# MEMS.net
KiCad netlist of a schematic drawn in Altium Designer
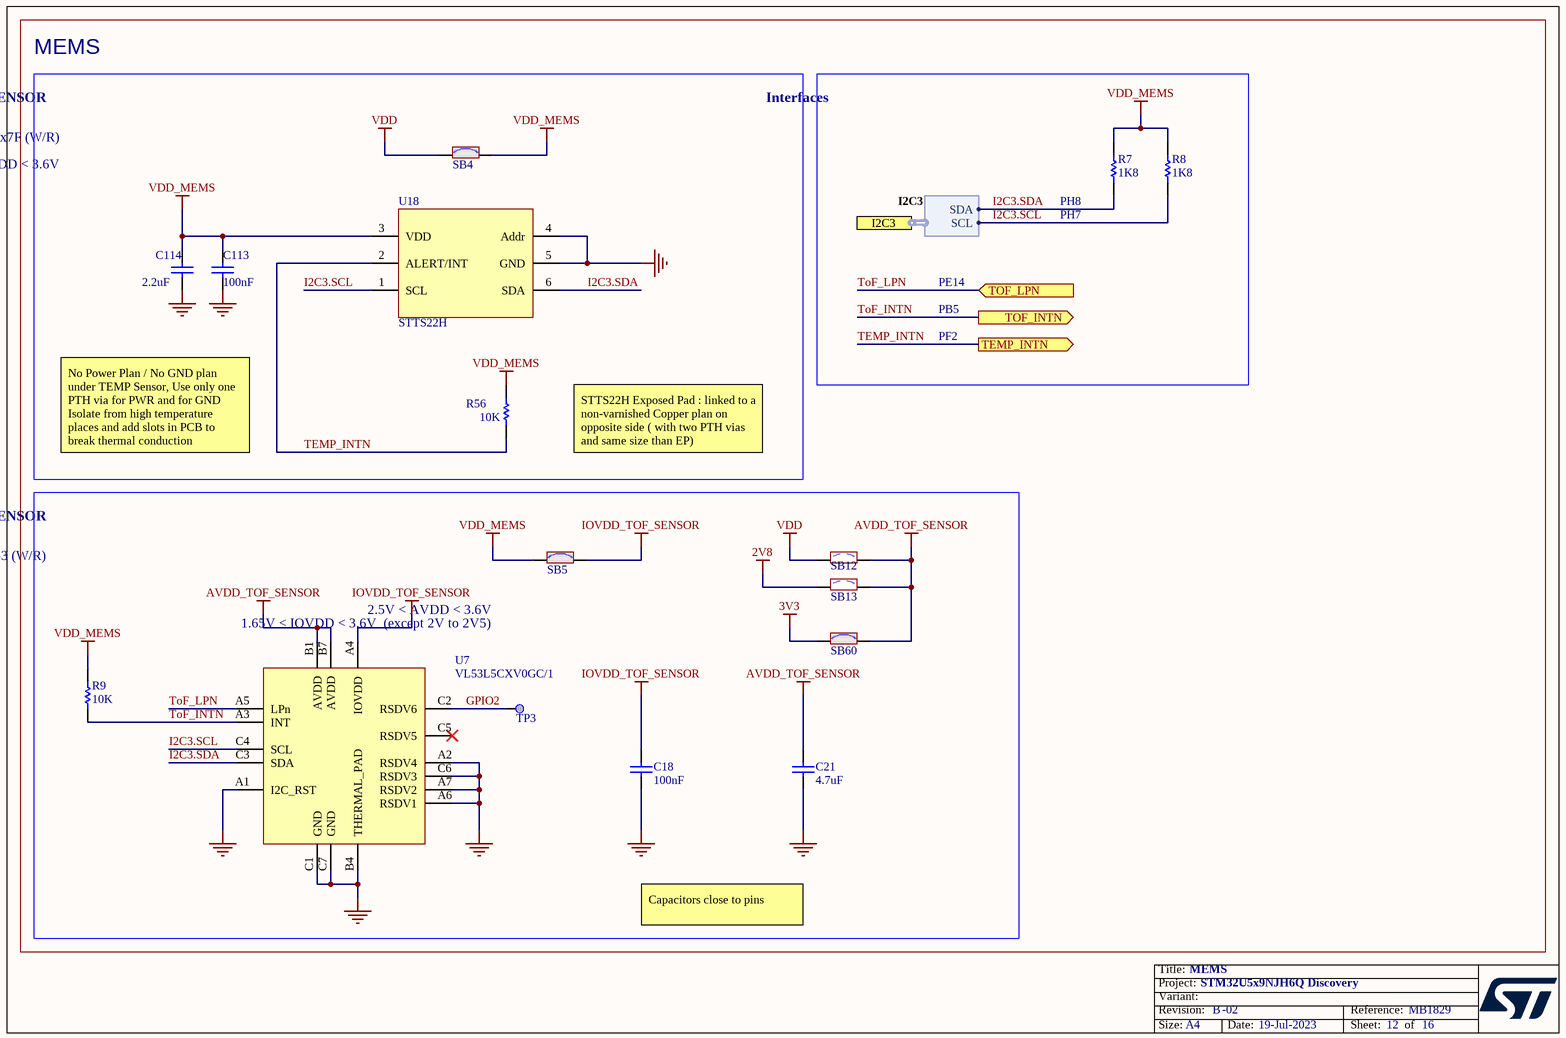
[diagram p0: MEMS.SchDoc]

(export (version "E")
  (design (tool "Eeschema 10.0.6"))
  (components
    (comp (ref "C18")
      (value "100nF")
      (footprint "MCD_PARTS:C0603")
      (description "Capacitor, MLCC, 100nF, 16V, X7R, +/-10%, 0603, T=0.8mm")
      (fields
        (field (name "INTERNAL_PART_NUMBER") "MCD-00211")
        (field (name "MANUFACTURER_PART_NUMBER") "CC0603KRX7R7BB104")
      )
      (libsource (lib "MCD_PARTS_database") (part "Capacitor"))
    )
    (comp (ref "C21")
      (value "4.7uF")
      (footprint "MCD_PARTS:C0603_H0P8")
      (description "Capacitor, MLCC, 4.7uF, 10V, X5R, +/-10%, 0603, T=0.8mm")
      (fields (field (name "INTERNAL_PART_NUMBER") "MCD-01721") (field (name "MANUFACTURER") "YAGEO"))
      (libsource (lib "MCD_PARTS_database") (part "Capacitor"))
    )
    (comp (ref "C113")
      (value "100nF")
      (footprint "MCD_PARTS:C0603")
      (description "Capacitor, MLCC, 100nF, 16V, X7R, +/-10%, 0603, T=0.8mm")
      (fields
        (field (name "INTERNAL_PART_NUMBER") "MCD-00211")
        (field (name "MANUFACTURER_PART_NUMBER") "CC0603KRX7R7BB104")
      )
      (libsource (lib "MCD_PARTS_database") (part "Capacitor"))
    )
    (comp (ref "C114")
      (value "2.2uF")
      (footprint "MCD_PARTS:C0603")
      (description "Capacitor, MLCC, 2.2uF, 10V, X5R, +/- 10%, 0603, T=0.8mm")
      (fields (field (name "INTERNAL_PART_NUMBER") "MCD-00012") (field (name "BMS_PART_NUMBER") "9142010"))
      (libsource (lib "MCD_PARTS_database") (part "Capacitor"))
    )
    (comp (ref "R7")
      (value "1K8")
      (footprint "MCD_PARTS:R0402")
      (description "Resistor, 1K8, 0402, +/-1%, 1/16W")
      (fields
        (field (name "INTERNAL_PART_NUMBER") "MCD-00409")
        (field (name "MANUFACTURER_PART_NUMBER") "RC0402FR-071K8L")
      )
      (libsource (lib "MCD_PARTS_database") (part "Resistor"))
    )
    (comp (ref "R8")
      (value "1K8")
      (footprint "MCD_PARTS:R0402")
      (description "Resistor, 1K8, 0402, +/-1%, 1/16W")
      (fields
        (field (name "INTERNAL_PART_NUMBER") "MCD-00409")
        (field (name "MANUFACTURER_PART_NUMBER") "RC0402FR-071K8L")
      )
      (libsource (lib "MCD_PARTS_database") (part "Resistor"))
    )
    (comp (ref "R9")
      (value "10K")
      (footprint "MCD_PARTS:R0603")
      (description "Resistor, 10K, 0603, +/-1%, 1/10W")
      (fields
        (field (name "INTERNAL_PART_NUMBER") "MCD-00220")
        (field (name "MANUFACTURER_PART_NUMBER") "RC0603FR-0710KL")
      )
      (libsource (lib "MCD_PARTS_database") (part "Resistor"))
    )
    (comp (ref "R56")
      (value "10K")
      (footprint "MCD_PARTS:R0603")
      (description "Resistor, 10K, 0603, +/-1%, 1/10W")
      (fields
        (field (name "INTERNAL_PART_NUMBER") "MCD-00220")
        (field (name "MANUFACTURER_PART_NUMBER") "RC0603FR-0710KL")
      )
      (libsource (lib "MCD_PARTS_database") (part "Resistor"))
    )
    (comp (ref "SB4")
      (value "SB_ON")
      (footprint "MCD_PARTS:SOLDER-BRIDGE_R0402-0R")
      (description "Solder Bridge 0402 ON")
      (fields
        (field (name "INTERNAL_PART_NUMBER") "MCD-01618")
        (field (name "MANUFACTURER_PART_NUMBER") "RC0402JR-070RL")
      )
      (libsource (lib "MCD_PARTS_database") (part "SB_ON"))
    )
    (comp (ref "SB5")
      (value "SB_ON")
      (footprint "MCD_PARTS:SOLDER-BRIDGE_R0402-0R")
      (description "Solder Bridge 0402 ON")
      (fields
        (field (name "INTERNAL_PART_NUMBER") "MCD-01618")
        (field (name "MANUFACTURER_PART_NUMBER") "RC0402JR-070RL")
      )
      (libsource (lib "MCD_PARTS_database") (part "SB_ON"))
    )
    (comp (ref "SB12")
      (value "SB_OFF")
      (footprint "MCD_PARTS:SOLDER-BRIDGE_R0402-0R")
      (description "Solder Bridge 0402 OFF")
      (fields
        (field (name "INTERNAL_PART_NUMBER") "MCD-02162")
        (field (name "MANUFACTURER_PART_NUMBER") "RC0402JR-070RL")
      )
      (libsource (lib "MCD_PARTS_database") (part "SB_OFF"))
    )
    (comp (ref "SB13")
      (value "SB_OFF")
      (footprint "MCD_PARTS:SOLDER-BRIDGE_R0402-0R")
      (description "Solder Bridge 0402 OFF")
      (fields
        (field (name "INTERNAL_PART_NUMBER") "MCD-02162")
        (field (name "MANUFACTURER_PART_NUMBER") "RC0402JR-070RL")
      )
      (libsource (lib "MCD_PARTS_database") (part "SB_OFF"))
    )
    (comp (ref "SB60")
      (value "SB_ON")
      (footprint "MCD_PARTS:SOLDER-BRIDGE_R0402-0R")
      (description "Solder Bridge 0402 ON")
      (fields
        (field (name "INTERNAL_PART_NUMBER") "MCD-01618")
        (field (name "MANUFACTURER_PART_NUMBER") "RC0402JR-070RL")
      )
      (libsource (lib "MCD_PARTS_database") (part "SB_ON"))
    )
    (comp (ref "TP3")
      (value "Test Point")
      (footprint "MCD_PARTS:TP_SMD_1MM")
      (description "Test Point 1mm")
      (fields
        (field (name "INTERNAL_PART_NUMBER") "MCD-00074")
        (field (name "MANUFACTURER_PART_NUMBER") "n/a")
      )
      (libsource (lib "MCD_PARTS_database") (part "Test Point"))
    )
    (comp (ref "U7")
      (value "VL53L5CXV0GC/1")
      (footprint "MCD_PARTS:ICC_LGA16_6P4X3_P075_H1P5")
      (description "Time-of-Flight 8x8 multizone ranging sensor with wide field of view")
      (fields
        (field (name "INTERNAL_PART_NUMBER") "MCD-02590")
        (field (name "MANUFACTURER") "STMICROELECTRONICS")
      )
      (libsource (lib "MCD_PARTS_database") (part "VL53L5CXV0GC/1"))
    )
    (comp (ref "U18")
      (value "STTS22H")
      (footprint "MCD_PARTS:ICC_UDFN6-EPAD_2X2_P065")
      (description "temperature sensor")
      (fields
        (field (name "INTERNAL_PART_NUMBER") "MCD-02159")
        (field (name "MANUFACTURER") "STMICROELECTRONICS")
      )
      (libsource (lib "MCD_PARTS_database") (part "STTS22H"))
    )
  )
  (nets
    (net (code "2") (name "/GPIO2") (class "Default")
      (node (ref "TP3") (pin "1") (pinfunction "1_1") (pintype "passive"))
      (node (ref "U7") (pin "C2") (pinfunction "RSDV6_C2") (pintype "passive"))
    )
    (net (code "3") (name "/I2C3.SCL") (class "Default")
      (node (ref "R8") (pin "1") (pinfunction "1_1") (pintype "passive"))
      (node (ref "U18") (pin "1") (pinfunction "SCL_1") (pintype "passive"))
      (node (ref "U7") (pin "C4") (pinfunction "SCL_C4") (pintype "passive"))
    )
    (net (code "4") (name "/I2C3.SDA") (class "Default")
      (node (ref "R7") (pin "1") (pinfunction "1_1") (pintype "passive"))
      (node (ref "U18") (pin "6") (pinfunction "SDA_6") (pintype "passive"))
      (node (ref "U7") (pin "C3") (pinfunction "SDA_C3") (pintype "passive"))
    )
    (net (code "5") (name "/TEMP_INTN") (class "Default")
      (node (ref "R56") (pin "1") (pinfunction "1_1") (pintype "passive"))
      (node (ref "U18") (pin "2") (pinfunction "ALERT/INT_2") (pintype "passive"))
    )
    (net (code "6") (name "/ToF_INTN") (class "Default")
      (node (ref "R9") (pin "1") (pinfunction "1_1") (pintype "passive"))
      (node (ref "U7") (pin "A3") (pinfunction "INT_A3") (pintype "passive"))
    )
    (net (code "7") (name "/ToF_LPN") (class "Default")
      (node (ref "U7") (pin "A5") (pinfunction "LPn_A5") (pintype "passive"))
    )
    (net (code "9") (name "2V8") (class "Default")
      (node (ref "SB13") (pin "1") (pinfunction "1_1") (pintype "passive"))
    )
    (net (code "10") (name "3V3") (class "Default")
      (node (ref "SB60") (pin "1") (pinfunction "1_1") (pintype "passive"))
    )
    (net (code "11") (name "AVDD_TOF_SENSOR") (class "Default")
      (node (ref "C21") (pin "2") (pinfunction "2_2") (pintype "passive"))
      (node (ref "SB12") (pin "2") (pinfunction "2_2") (pintype "passive"))
      (node (ref "SB13") (pin "2") (pinfunction "2_2") (pintype "passive"))
      (node (ref "SB60") (pin "2") (pinfunction "2_2") (pintype "passive"))
      (node (ref "U7") (pin "B1") (pinfunction "AVDD_B1") (pintype "passive"))
      (node (ref "U7") (pin "B7") (pinfunction "AVDD_B7") (pintype "passive"))
    )
    (net (code "12") (name "GND") (class "Default")
      (node (ref "C113") (pin "2") (pinfunction "2_2") (pintype "passive"))
      (node (ref "C114") (pin "1") (pinfunction "1_1") (pintype "passive"))
      (node (ref "C18") (pin "2") (pinfunction "2_2") (pintype "passive"))
      (node (ref "C21") (pin "1") (pinfunction "1_1") (pintype "passive"))
      (node (ref "U18") (pin "4") (pinfunction "Addr_4") (pintype "passive"))
      (node (ref "U18") (pin "5") (pinfunction "GND_5") (pintype "passive"))
      (node (ref "U7") (pin "A1") (pinfunction "I2C_RST_A1") (pintype "passive"))
      (node (ref "U7") (pin "A2") (pinfunction "RSDV4_A2") (pintype "passive"))
      (node (ref "U7") (pin "A6") (pinfunction "RSDV1_A6") (pintype "passive"))
      (node (ref "U7") (pin "A7") (pinfunction "RSDV2_A7") (pintype "passive"))
      (node (ref "U7") (pin "B4") (pinfunction "THERMAL_PAD_B4") (pintype "passive"))
      (node (ref "U7") (pin "C1") (pinfunction "GND_C1") (pintype "passive"))
      (node (ref "U7") (pin "C6") (pinfunction "RSDV3_C6") (pintype "passive"))
      (node (ref "U7") (pin "C7") (pinfunction "GND_C7") (pintype "passive"))
    )
    (net (code "13") (name "IOVDD_TOF_SENSOR") (class "Default")
      (node (ref "C18") (pin "1") (pinfunction "1_1") (pintype "passive"))
      (node (ref "SB5") (pin "2") (pinfunction "2_2") (pintype "passive"))
      (node (ref "U7") (pin "A4") (pinfunction "IOVDD_A4") (pintype "passive"))
    )
    (net (code "14") (name "VDD") (class "Default")
      (node (ref "SB12") (pin "1") (pinfunction "1_1") (pintype "passive"))
      (node (ref "SB4") (pin "1") (pinfunction "1_1") (pintype "passive"))
    )
    (net (code "15") (name "VDD_MEMS") (class "Default")
      (node (ref "C113") (pin "1") (pinfunction "1_1") (pintype "passive"))
      (node (ref "C114") (pin "2") (pinfunction "2_2") (pintype "passive"))
      (node (ref "R56") (pin "2") (pinfunction "2_2") (pintype "passive"))
      (node (ref "R7") (pin "2") (pinfunction "2_2") (pintype "passive"))
      (node (ref "R8") (pin "2") (pinfunction "2_2") (pintype "passive"))
      (node (ref "R9") (pin "2") (pinfunction "2_2") (pintype "passive"))
      (node (ref "SB4") (pin "2") (pinfunction "2_2") (pintype "passive"))
      (node (ref "SB5") (pin "1") (pinfunction "1_1") (pintype "passive"))
      (node (ref "U18") (pin "3") (pinfunction "VDD_3") (pintype "passive"))
    )
    (net (code "16") (name "unconnected-(U7-RSDV5-PadC5)") (class "Default")
      (node (ref "U7") (pin "C5") (pinfunction "RSDV5_C5") (pintype "passive+no_connect"))
    )
  )
)
